# OP-80A.net
KiCad netlist of a schematic drawn in EAGLE
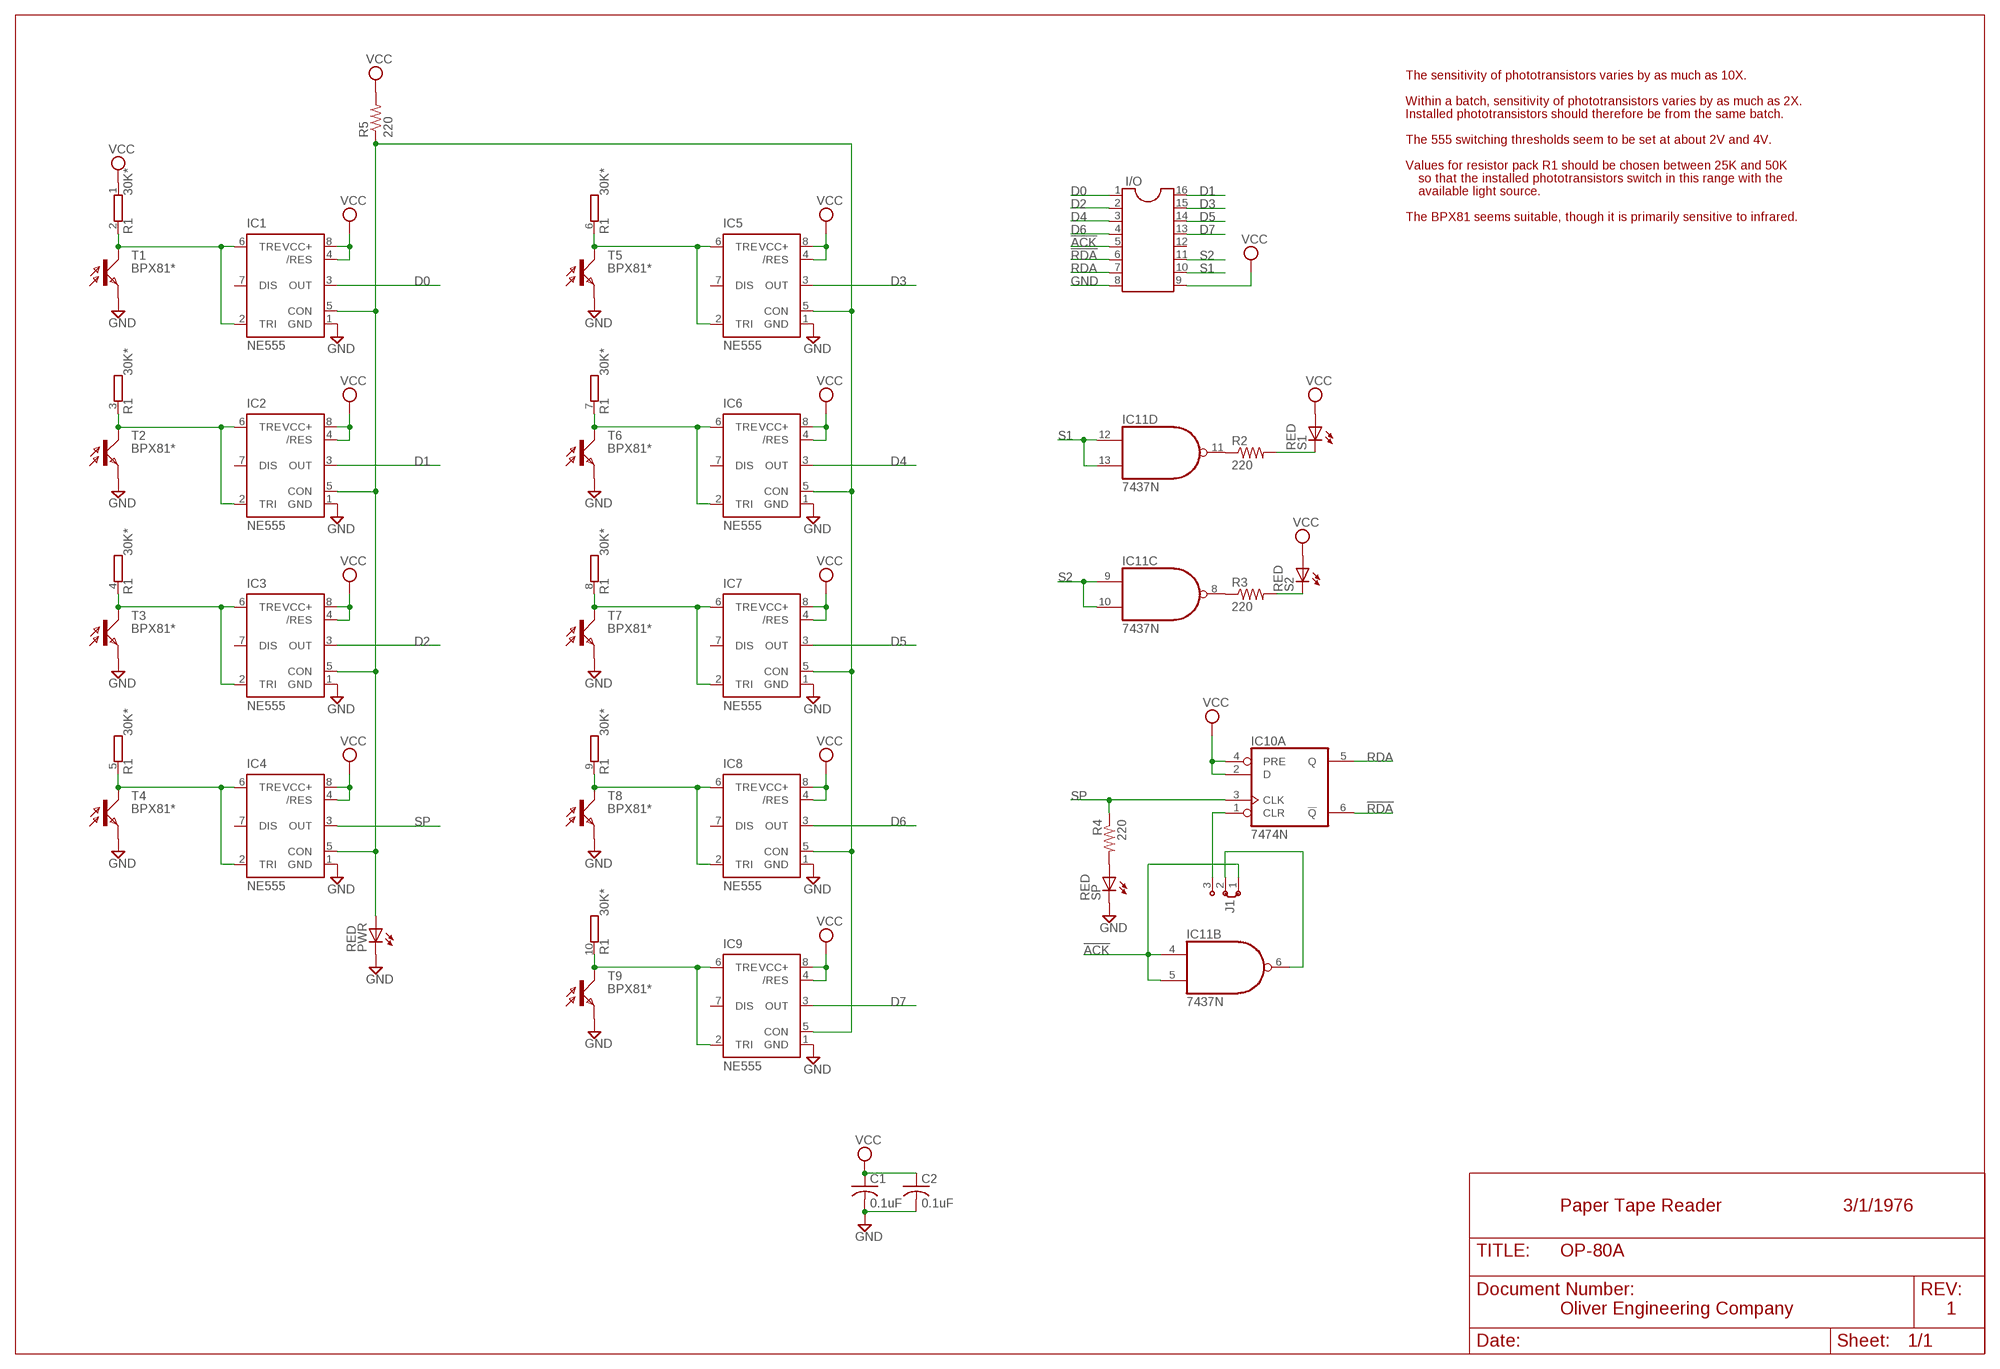
[diagram p0: schematic, sheet 1]

(export (version "E")
  (design (tool "Eeschema 10.0.6"))
  (components
    (comp (ref "C1")
      (value "0.1uF")
      (footprint "eagle-import:C050-030X075")
      (libsource (lib "eagle-import") (part "C-US050-030X075"))
    )
    (comp (ref "C2")
      (value "0.1uF")
      (footprint "eagle-import:C050-030X075")
      (libsource (lib "eagle-import") (part "C-US050-030X075"))
    )
    (comp (ref "I/O")
      (value "DIL16S")
      (footprint "eagle-import:SOCKET-16")
      (libsource (lib "eagle-import") (part "DIL16S"))
    )
    (comp (ref "IC1")
      (value "NE555")
      (footprint "eagle-import:DIL-08")
      (fields (field (name "MF") "Arrow Electronics") (field (name "MPN") "NE555N"))
      (libsource (lib "eagle-import") (part "NE555"))
    )
    (comp (ref "IC2")
      (value "NE555")
      (footprint "eagle-import:DIL-08")
      (fields (field (name "MF") "Arrow Electronics") (field (name "MPN") "NE555N"))
      (libsource (lib "eagle-import") (part "NE555"))
    )
    (comp (ref "IC3")
      (value "NE555")
      (footprint "eagle-import:DIL-08")
      (fields (field (name "MF") "Arrow Electronics") (field (name "MPN") "NE555N"))
      (libsource (lib "eagle-import") (part "NE555"))
    )
    (comp (ref "IC4")
      (value "NE555")
      (footprint "eagle-import:DIL-08")
      (fields (field (name "MF") "Arrow Electronics") (field (name "MPN") "NE555N"))
      (libsource (lib "eagle-import") (part "NE555"))
    )
    (comp (ref "IC5")
      (value "NE555")
      (footprint "eagle-import:DIL-08")
      (fields (field (name "MF") "Arrow Electronics") (field (name "MPN") "NE555N"))
      (libsource (lib "eagle-import") (part "NE555"))
    )
    (comp (ref "IC6")
      (value "NE555")
      (footprint "eagle-import:DIL-08")
      (fields (field (name "MF") "Arrow Electronics") (field (name "MPN") "NE555N"))
      (libsource (lib "eagle-import") (part "NE555"))
    )
    (comp (ref "IC7")
      (value "NE555")
      (footprint "eagle-import:DIL-08")
      (fields (field (name "MF") "Arrow Electronics") (field (name "MPN") "NE555N"))
      (libsource (lib "eagle-import") (part "NE555"))
    )
    (comp (ref "IC8")
      (value "NE555")
      (footprint "eagle-import:DIL-08")
      (fields (field (name "MF") "Arrow Electronics") (field (name "MPN") "NE555N"))
      (libsource (lib "eagle-import") (part "NE555"))
    )
    (comp (ref "IC9")
      (value "NE555")
      (footprint "eagle-import:DIL-08")
      (fields (field (name "MF") "Arrow Electronics") (field (name "MPN") "NE555N"))
      (libsource (lib "eagle-import") (part "NE555"))
    )
    (comp (ref "IC10")
      (value "7474N")
      (footprint "eagle-import:DIL14")
      (libsource (lib "eagle-import") (part "7474NLS"))
    )
    (comp (ref "IC11")
      (value "7437N")
      (footprint "eagle-import:DIL14")
      (libsource (lib "eagle-import") (part "7437N"))
    )
    (comp (ref "J1")
      (value "J2X5MM")
      (footprint "eagle-import:05C")
      (libsource (lib "eagle-import") (part "J2X5MM"))
    )
    (comp (ref "PWR")
      (value "RED")
      (footprint "eagle-import:LED5MM")
      (libsource (lib "eagle-import") (part "LED5MM"))
    )
    (comp (ref "R1")
      (value "30K*")
      (footprint "eagle-import:SIL10")
      (libsource (lib "eagle-import") (part "GE09RP"))
    )
    (comp (ref "R2")
      (value "220")
      (footprint "eagle-import:0207_10")
      (libsource (lib "eagle-import") (part "R-US_0207/10"))
    )
    (comp (ref "R3")
      (value "220")
      (footprint "eagle-import:0207_10")
      (libsource (lib "eagle-import") (part "R-US_0207/10"))
    )
    (comp (ref "R4")
      (value "220")
      (footprint "eagle-import:0207_10")
      (libsource (lib "eagle-import") (part "R-US_0207/10"))
    )
    (comp (ref "R5")
      (value "220")
      (footprint "eagle-import:0207_10")
      (libsource (lib "eagle-import") (part "R-US_0207/10"))
    )
    (comp (ref "S1")
      (value "RED")
      (footprint "eagle-import:LED5MM")
      (libsource (lib "eagle-import") (part "LED5MM"))
    )
    (comp (ref "S2")
      (value "RED")
      (footprint "eagle-import:LED5MM")
      (libsource (lib "eagle-import") (part "LED5MM"))
    )
    (comp (ref "SP")
      (value "RED")
      (footprint "eagle-import:LED5MM")
      (libsource (lib "eagle-import") (part "LED5MM"))
    )
    (comp (ref "T1")
      (value "BPX81*")
      (footprint "eagle-import:BPX81")
      (libsource (lib "eagle-import") (part "BPX81"))
    )
    (comp (ref "T2")
      (value "BPX81*")
      (footprint "eagle-import:BPX81")
      (libsource (lib "eagle-import") (part "BPX81"))
    )
    (comp (ref "T3")
      (value "BPX81*")
      (footprint "eagle-import:BPX81")
      (libsource (lib "eagle-import") (part "BPX81"))
    )
    (comp (ref "T4")
      (value "BPX81*")
      (footprint "eagle-import:BPX81")
      (libsource (lib "eagle-import") (part "BPX81"))
    )
    (comp (ref "T5")
      (value "BPX81*")
      (footprint "eagle-import:BPX81")
      (libsource (lib "eagle-import") (part "BPX81"))
    )
    (comp (ref "T6")
      (value "BPX81*")
      (footprint "eagle-import:BPX81")
      (libsource (lib "eagle-import") (part "BPX81"))
    )
    (comp (ref "T7")
      (value "BPX81*")
      (footprint "eagle-import:BPX81")
      (libsource (lib "eagle-import") (part "BPX81"))
    )
    (comp (ref "T8")
      (value "BPX81*")
      (footprint "eagle-import:BPX81")
      (libsource (lib "eagle-import") (part "BPX81"))
    )
    (comp (ref "T9")
      (value "BPX81*")
      (footprint "eagle-import:BPX81")
      (libsource (lib "eagle-import") (part "BPX81"))
    )
  )
  (nets
    (net (code "1") (name "/D0") (class "Default")
      (node (ref "I/O") (pin "1") (pinfunction "1_1") (pintype "passive"))
      (node (ref "IC1") (pin "3") (pinfunction "OUT_3") (pintype "output"))
    )
    (net (code "2") (name "/D1") (class "Default")
      (node (ref "I/O") (pin "16") (pinfunction "16_16") (pintype "passive"))
      (node (ref "IC2") (pin "3") (pinfunction "OUT_3") (pintype "output"))
    )
    (net (code "3") (name "/D2") (class "Default")
      (node (ref "I/O") (pin "2") (pinfunction "2_2") (pintype "passive"))
      (node (ref "IC3") (pin "3") (pinfunction "OUT_3") (pintype "output"))
    )
    (net (code "4") (name "/D3") (class "Default")
      (node (ref "I/O") (pin "15") (pinfunction "15_15") (pintype "passive"))
      (node (ref "IC5") (pin "3") (pinfunction "OUT_3") (pintype "output"))
    )
    (net (code "5") (name "/D4") (class "Default")
      (node (ref "I/O") (pin "3") (pinfunction "3_3") (pintype "passive"))
      (node (ref "IC6") (pin "3") (pinfunction "OUT_3") (pintype "output"))
    )
    (net (code "6") (name "/D5") (class "Default")
      (node (ref "I/O") (pin "14") (pinfunction "14_14") (pintype "passive"))
      (node (ref "IC7") (pin "3") (pinfunction "OUT_3") (pintype "output"))
    )
    (net (code "7") (name "/D6") (class "Default")
      (node (ref "I/O") (pin "4") (pinfunction "4_4") (pintype "passive"))
      (node (ref "IC8") (pin "3") (pinfunction "OUT_3") (pintype "output"))
    )
    (net (code "8") (name "/D7") (class "Default")
      (node (ref "I/O") (pin "13") (pinfunction "13_13") (pintype "passive"))
      (node (ref "IC9") (pin "3") (pinfunction "OUT_3") (pintype "output"))
    )
    (net (code "9") (name "/RDA") (class "Default")
      (node (ref "I/O") (pin "7") (pinfunction "7_7") (pintype "passive"))
      (node (ref "IC10") (pin "5") (pinfunction "Q_5") (pintype "output"))
    )
    (net (code "10") (name "/S1") (class "Default")
      (node (ref "I/O") (pin "10") (pinfunction "10_10") (pintype "passive"))
      (node (ref "IC11") (pin "12") (pinfunction "I0_12") (pintype "input"))
      (node (ref "IC11") (pin "13") (pinfunction "I1_13") (pintype "input"))
    )
    (net (code "11") (name "/S2") (class "Default")
      (node (ref "I/O") (pin "11") (pinfunction "11_11") (pintype "passive"))
      (node (ref "IC11") (pin "10") (pinfunction "I1_10") (pintype "input"))
      (node (ref "IC11") (pin "9") (pinfunction "I0_9") (pintype "input"))
    )
    (net (code "12") (name "/SP") (class "Default")
      (node (ref "IC10") (pin "3") (pinfunction "CLK_3") (pintype "input"))
      (node (ref "IC4") (pin "3") (pinfunction "OUT_3") (pintype "output"))
      (node (ref "R4") (pin "1") (pinfunction "1_1") (pintype "passive"))
    )
    (net (code "13") (name "/~{ACK}") (class "Default")
      (node (ref "I/O") (pin "5") (pinfunction "5_5") (pintype "passive"))
      (node (ref "IC11") (pin "4") (pinfunction "I0_4") (pintype "input"))
      (node (ref "IC11") (pin "5") (pinfunction "I1_5") (pintype "input"))
      (node (ref "J1") (pin "1") (pinfunction "1_1") (pintype "passive"))
    )
    (net (code "14") (name "/~{RDA}") (class "Default")
      (node (ref "I/O") (pin "6") (pinfunction "6_6") (pintype "passive"))
      (node (ref "IC10") (pin "6") (pinfunction "~{Q}_6") (pintype "output"))
    )
    (net (code "15") (name "GND") (class "Default")
      (node (ref "C1") (pin "2") (pinfunction "2_2") (pintype "passive"))
      (node (ref "C2") (pin "2") (pinfunction "2_2") (pintype "passive"))
      (node (ref "I/O") (pin "8") (pinfunction "8_8") (pintype "passive"))
      (node (ref "IC1") (pin "1") (pinfunction "GND_1") (pintype "power_in"))
      (node (ref "IC2") (pin "1") (pinfunction "GND_1") (pintype "power_in"))
      (node (ref "IC3") (pin "1") (pinfunction "GND_1") (pintype "power_in"))
      (node (ref "IC4") (pin "1") (pinfunction "GND_1") (pintype "power_in"))
      (node (ref "IC5") (pin "1") (pinfunction "GND_1") (pintype "power_in"))
      (node (ref "IC6") (pin "1") (pinfunction "GND_1") (pintype "power_in"))
      (node (ref "IC7") (pin "1") (pinfunction "GND_1") (pintype "power_in"))
      (node (ref "IC8") (pin "1") (pinfunction "GND_1") (pintype "power_in"))
      (node (ref "IC9") (pin "1") (pinfunction "GND_1") (pintype "power_in"))
      (node (ref "PWR") (pin "K") (pinfunction "C_K") (pintype "passive"))
      (node (ref "SP") (pin "K") (pinfunction "C_K") (pintype "passive"))
      (node (ref "T1") (pin "E") (pinfunction "E_E") (pintype "passive"))
      (node (ref "T2") (pin "E") (pinfunction "E_E") (pintype "passive"))
      (node (ref "T3") (pin "E") (pinfunction "E_E") (pintype "passive"))
      (node (ref "T4") (pin "E") (pinfunction "E_E") (pintype "passive"))
      (node (ref "T5") (pin "E") (pinfunction "E_E") (pintype "passive"))
      (node (ref "T6") (pin "E") (pinfunction "E_E") (pintype "passive"))
      (node (ref "T7") (pin "E") (pinfunction "E_E") (pintype "passive"))
      (node (ref "T8") (pin "E") (pinfunction "E_E") (pintype "passive"))
      (node (ref "T9") (pin "E") (pinfunction "E_E") (pintype "passive"))
    )
    (net (code "16") (name "Net-(IC1-CON)") (class "Default")
      (node (ref "IC1") (pin "5") (pinfunction "CON_5") (pintype "input"))
      (node (ref "IC2") (pin "5") (pinfunction "CON_5") (pintype "input"))
      (node (ref "IC3") (pin "5") (pinfunction "CON_5") (pintype "input"))
      (node (ref "IC4") (pin "5") (pinfunction "CON_5") (pintype "input"))
      (node (ref "IC5") (pin "5") (pinfunction "CON_5") (pintype "input"))
      (node (ref "IC6") (pin "5") (pinfunction "CON_5") (pintype "input"))
      (node (ref "IC7") (pin "5") (pinfunction "CON_5") (pintype "input"))
      (node (ref "IC8") (pin "5") (pinfunction "CON_5") (pintype "input"))
      (node (ref "IC9") (pin "5") (pinfunction "CON_5") (pintype "input"))
      (node (ref "PWR") (pin "A") (pinfunction "A_A") (pintype "passive"))
      (node (ref "R5") (pin "1") (pinfunction "1_1") (pintype "passive"))
    )
    (net (code "17") (name "Net-(IC1-TRE)") (class "Default")
      (node (ref "IC1") (pin "2") (pinfunction "TRI_2") (pintype "input"))
      (node (ref "IC1") (pin "6") (pinfunction "TRE_6") (pintype "input"))
      (node (ref "R1") (pin "2") (pinfunction "2_2") (pintype "passive"))
      (node (ref "T1") (pin "C") (pinfunction "C_C") (pintype "passive"))
    )
    (net (code "18") (name "Net-(IC2-TRE)") (class "Default")
      (node (ref "IC2") (pin "2") (pinfunction "TRI_2") (pintype "input"))
      (node (ref "IC2") (pin "6") (pinfunction "TRE_6") (pintype "input"))
      (node (ref "R1") (pin "3") (pinfunction "2_3") (pintype "passive"))
      (node (ref "T2") (pin "C") (pinfunction "C_C") (pintype "passive"))
    )
    (net (code "19") (name "Net-(IC3-TRE)") (class "Default")
      (node (ref "IC3") (pin "2") (pinfunction "TRI_2") (pintype "input"))
      (node (ref "IC3") (pin "6") (pinfunction "TRE_6") (pintype "input"))
      (node (ref "R1") (pin "4") (pinfunction "2_4") (pintype "passive"))
      (node (ref "T3") (pin "C") (pinfunction "C_C") (pintype "passive"))
    )
    (net (code "20") (name "Net-(IC4-TRE)") (class "Default")
      (node (ref "IC4") (pin "2") (pinfunction "TRI_2") (pintype "input"))
      (node (ref "IC4") (pin "6") (pinfunction "TRE_6") (pintype "input"))
      (node (ref "R1") (pin "5") (pinfunction "2_5") (pintype "passive"))
      (node (ref "T4") (pin "C") (pinfunction "C_C") (pintype "passive"))
    )
    (net (code "21") (name "Net-(IC5-TRE)") (class "Default")
      (node (ref "IC5") (pin "2") (pinfunction "TRI_2") (pintype "input"))
      (node (ref "IC5") (pin "6") (pinfunction "TRE_6") (pintype "input"))
      (node (ref "R1") (pin "6") (pinfunction "2_6") (pintype "passive"))
      (node (ref "T5") (pin "C") (pinfunction "C_C") (pintype "passive"))
    )
    (net (code "22") (name "Net-(IC6-TRE)") (class "Default")
      (node (ref "IC6") (pin "2") (pinfunction "TRI_2") (pintype "input"))
      (node (ref "IC6") (pin "6") (pinfunction "TRE_6") (pintype "input"))
      (node (ref "R1") (pin "7") (pinfunction "2_7") (pintype "passive"))
      (node (ref "T6") (pin "C") (pinfunction "C_C") (pintype "passive"))
    )
    (net (code "23") (name "Net-(IC7-TRE)") (class "Default")
      (node (ref "IC7") (pin "2") (pinfunction "TRI_2") (pintype "input"))
      (node (ref "IC7") (pin "6") (pinfunction "TRE_6") (pintype "input"))
      (node (ref "R1") (pin "8") (pinfunction "2_8") (pintype "passive"))
      (node (ref "T7") (pin "C") (pinfunction "C_C") (pintype "passive"))
    )
    (net (code "24") (name "Net-(IC8-TRE)") (class "Default")
      (node (ref "IC8") (pin "2") (pinfunction "TRI_2") (pintype "input"))
      (node (ref "IC8") (pin "6") (pinfunction "TRE_6") (pintype "input"))
      (node (ref "R1") (pin "9") (pinfunction "2_9") (pintype "passive"))
      (node (ref "T8") (pin "C") (pinfunction "C_C") (pintype "passive"))
    )
    (net (code "25") (name "Net-(IC9-TRE)") (class "Default")
      (node (ref "IC9") (pin "2") (pinfunction "TRI_2") (pintype "input"))
      (node (ref "IC9") (pin "6") (pinfunction "TRE_6") (pintype "input"))
      (node (ref "R1") (pin "10") (pinfunction "2_10") (pintype "passive"))
      (node (ref "T9") (pin "C") (pinfunction "C_C") (pintype "passive"))
    )
    (net (code "26") (name "Net-(IC10A-CLR)") (class "Default")
      (node (ref "IC10") (pin "1") (pinfunction "CLR_1") (pintype "input"))
      (node (ref "J1") (pin "3") (pinfunction "3_3") (pintype "passive"))
    )
    (net (code "27") (name "Net-(IC11B-O)") (class "Default")
      (node (ref "IC11") (pin "6") (pinfunction "O_6") (pintype "output"))
      (node (ref "J1") (pin "2") (pinfunction "2_2") (pintype "passive"))
    )
    (net (code "28") (name "Net-(IC11C-O)") (class "Default")
      (node (ref "IC11") (pin "8") (pinfunction "O_8") (pintype "output"))
      (node (ref "R3") (pin "1") (pinfunction "1_1") (pintype "passive"))
    )
    (net (code "29") (name "Net-(IC11D-O)") (class "Default")
      (node (ref "IC11") (pin "11") (pinfunction "O_11") (pintype "output"))
      (node (ref "R2") (pin "1") (pinfunction "1_1") (pintype "passive"))
    )
    (net (code "30") (name "Net-(R4-Pad2)") (class "Default")
      (node (ref "R4") (pin "2") (pinfunction "2_2") (pintype "passive"))
      (node (ref "SP") (pin "A") (pinfunction "A_A") (pintype "passive"))
    )
    (net (code "31") (name "Net-(S1-C)") (class "Default")
      (node (ref "R2") (pin "2") (pinfunction "2_2") (pintype "passive"))
      (node (ref "S1") (pin "K") (pinfunction "C_K") (pintype "passive"))
    )
    (net (code "32") (name "Net-(S2-C)") (class "Default")
      (node (ref "R3") (pin "2") (pinfunction "2_2") (pintype "passive"))
      (node (ref "S2") (pin "K") (pinfunction "C_K") (pintype "passive"))
    )
    (net (code "33") (name "VCC") (class "Default")
      (node (ref "C1") (pin "1") (pinfunction "1_1") (pintype "passive"))
      (node (ref "C2") (pin "1") (pinfunction "1_1") (pintype "passive"))
      (node (ref "I/O") (pin "9") (pinfunction "9_9") (pintype "passive"))
      (node (ref "IC1") (pin "4") (pinfunction "/RES_4") (pintype "input"))
      (node (ref "IC1") (pin "8") (pinfunction "VCC+_8") (pintype "power_in"))
      (node (ref "IC10") (pin "2") (pinfunction "D_2") (pintype "input"))
      (node (ref "IC10") (pin "4") (pinfunction "PRE_4") (pintype "input"))
      (node (ref "IC2") (pin "4") (pinfunction "/RES_4") (pintype "input"))
      (node (ref "IC2") (pin "8") (pinfunction "VCC+_8") (pintype "power_in"))
      (node (ref "IC3") (pin "4") (pinfunction "/RES_4") (pintype "input"))
      (node (ref "IC3") (pin "8") (pinfunction "VCC+_8") (pintype "power_in"))
      (node (ref "IC4") (pin "4") (pinfunction "/RES_4") (pintype "input"))
      (node (ref "IC4") (pin "8") (pinfunction "VCC+_8") (pintype "power_in"))
      (node (ref "IC5") (pin "4") (pinfunction "/RES_4") (pintype "input"))
      (node (ref "IC5") (pin "8") (pinfunction "VCC+_8") (pintype "power_in"))
      (node (ref "IC6") (pin "4") (pinfunction "/RES_4") (pintype "input"))
      (node (ref "IC6") (pin "8") (pinfunction "VCC+_8") (pintype "power_in"))
      (node (ref "IC7") (pin "4") (pinfunction "/RES_4") (pintype "input"))
      (node (ref "IC7") (pin "8") (pinfunction "VCC+_8") (pintype "power_in"))
      (node (ref "IC8") (pin "4") (pinfunction "/RES_4") (pintype "input"))
      (node (ref "IC8") (pin "8") (pinfunction "VCC+_8") (pintype "power_in"))
      (node (ref "IC9") (pin "4") (pinfunction "/RES_4") (pintype "input"))
      (node (ref "IC9") (pin "8") (pinfunction "VCC+_8") (pintype "power_in"))
      (node (ref "R1") (pin "1") (pinfunction "1_1") (pintype "passive"))
      (node (ref "R5") (pin "2") (pinfunction "2_2") (pintype "passive"))
      (node (ref "S1") (pin "A") (pinfunction "A_A") (pintype "passive"))
      (node (ref "S2") (pin "A") (pinfunction "A_A") (pintype "passive"))
    )
    (net (code "34") (name "unconnected-(I/O-Pad12)") (class "Default")
      (node (ref "I/O") (pin "12") (pinfunction "12_12") (pintype "passive"))
    )
    (net (code "35") (name "unconnected-(IC1-DIS-Pad7)") (class "Default")
      (node (ref "IC1") (pin "7") (pinfunction "DIS_7") (pintype "output"))
    )
    (net (code "36") (name "unconnected-(IC2-DIS-Pad7)") (class "Default")
      (node (ref "IC2") (pin "7") (pinfunction "DIS_7") (pintype "output"))
    )
    (net (code "37") (name "unconnected-(IC3-DIS-Pad7)") (class "Default")
      (node (ref "IC3") (pin "7") (pinfunction "DIS_7") (pintype "output"))
    )
    (net (code "38") (name "unconnected-(IC4-DIS-Pad7)") (class "Default")
      (node (ref "IC4") (pin "7") (pinfunction "DIS_7") (pintype "output"))
    )
    (net (code "39") (name "unconnected-(IC5-DIS-Pad7)") (class "Default")
      (node (ref "IC5") (pin "7") (pinfunction "DIS_7") (pintype "output"))
    )
    (net (code "40") (name "unconnected-(IC6-DIS-Pad7)") (class "Default")
      (node (ref "IC6") (pin "7") (pinfunction "DIS_7") (pintype "output"))
    )
    (net (code "41") (name "unconnected-(IC7-DIS-Pad7)") (class "Default")
      (node (ref "IC7") (pin "7") (pinfunction "DIS_7") (pintype "output"))
    )
    (net (code "42") (name "unconnected-(IC8-DIS-Pad7)") (class "Default")
      (node (ref "IC8") (pin "7") (pinfunction "DIS_7") (pintype "output"))
    )
    (net (code "43") (name "unconnected-(IC9-DIS-Pad7)") (class "Default")
      (node (ref "IC9") (pin "7") (pinfunction "DIS_7") (pintype "output"))
    )
  )
)
